# lime-lemon.net
KiCad netlist of a schematic drawn in EAGLE
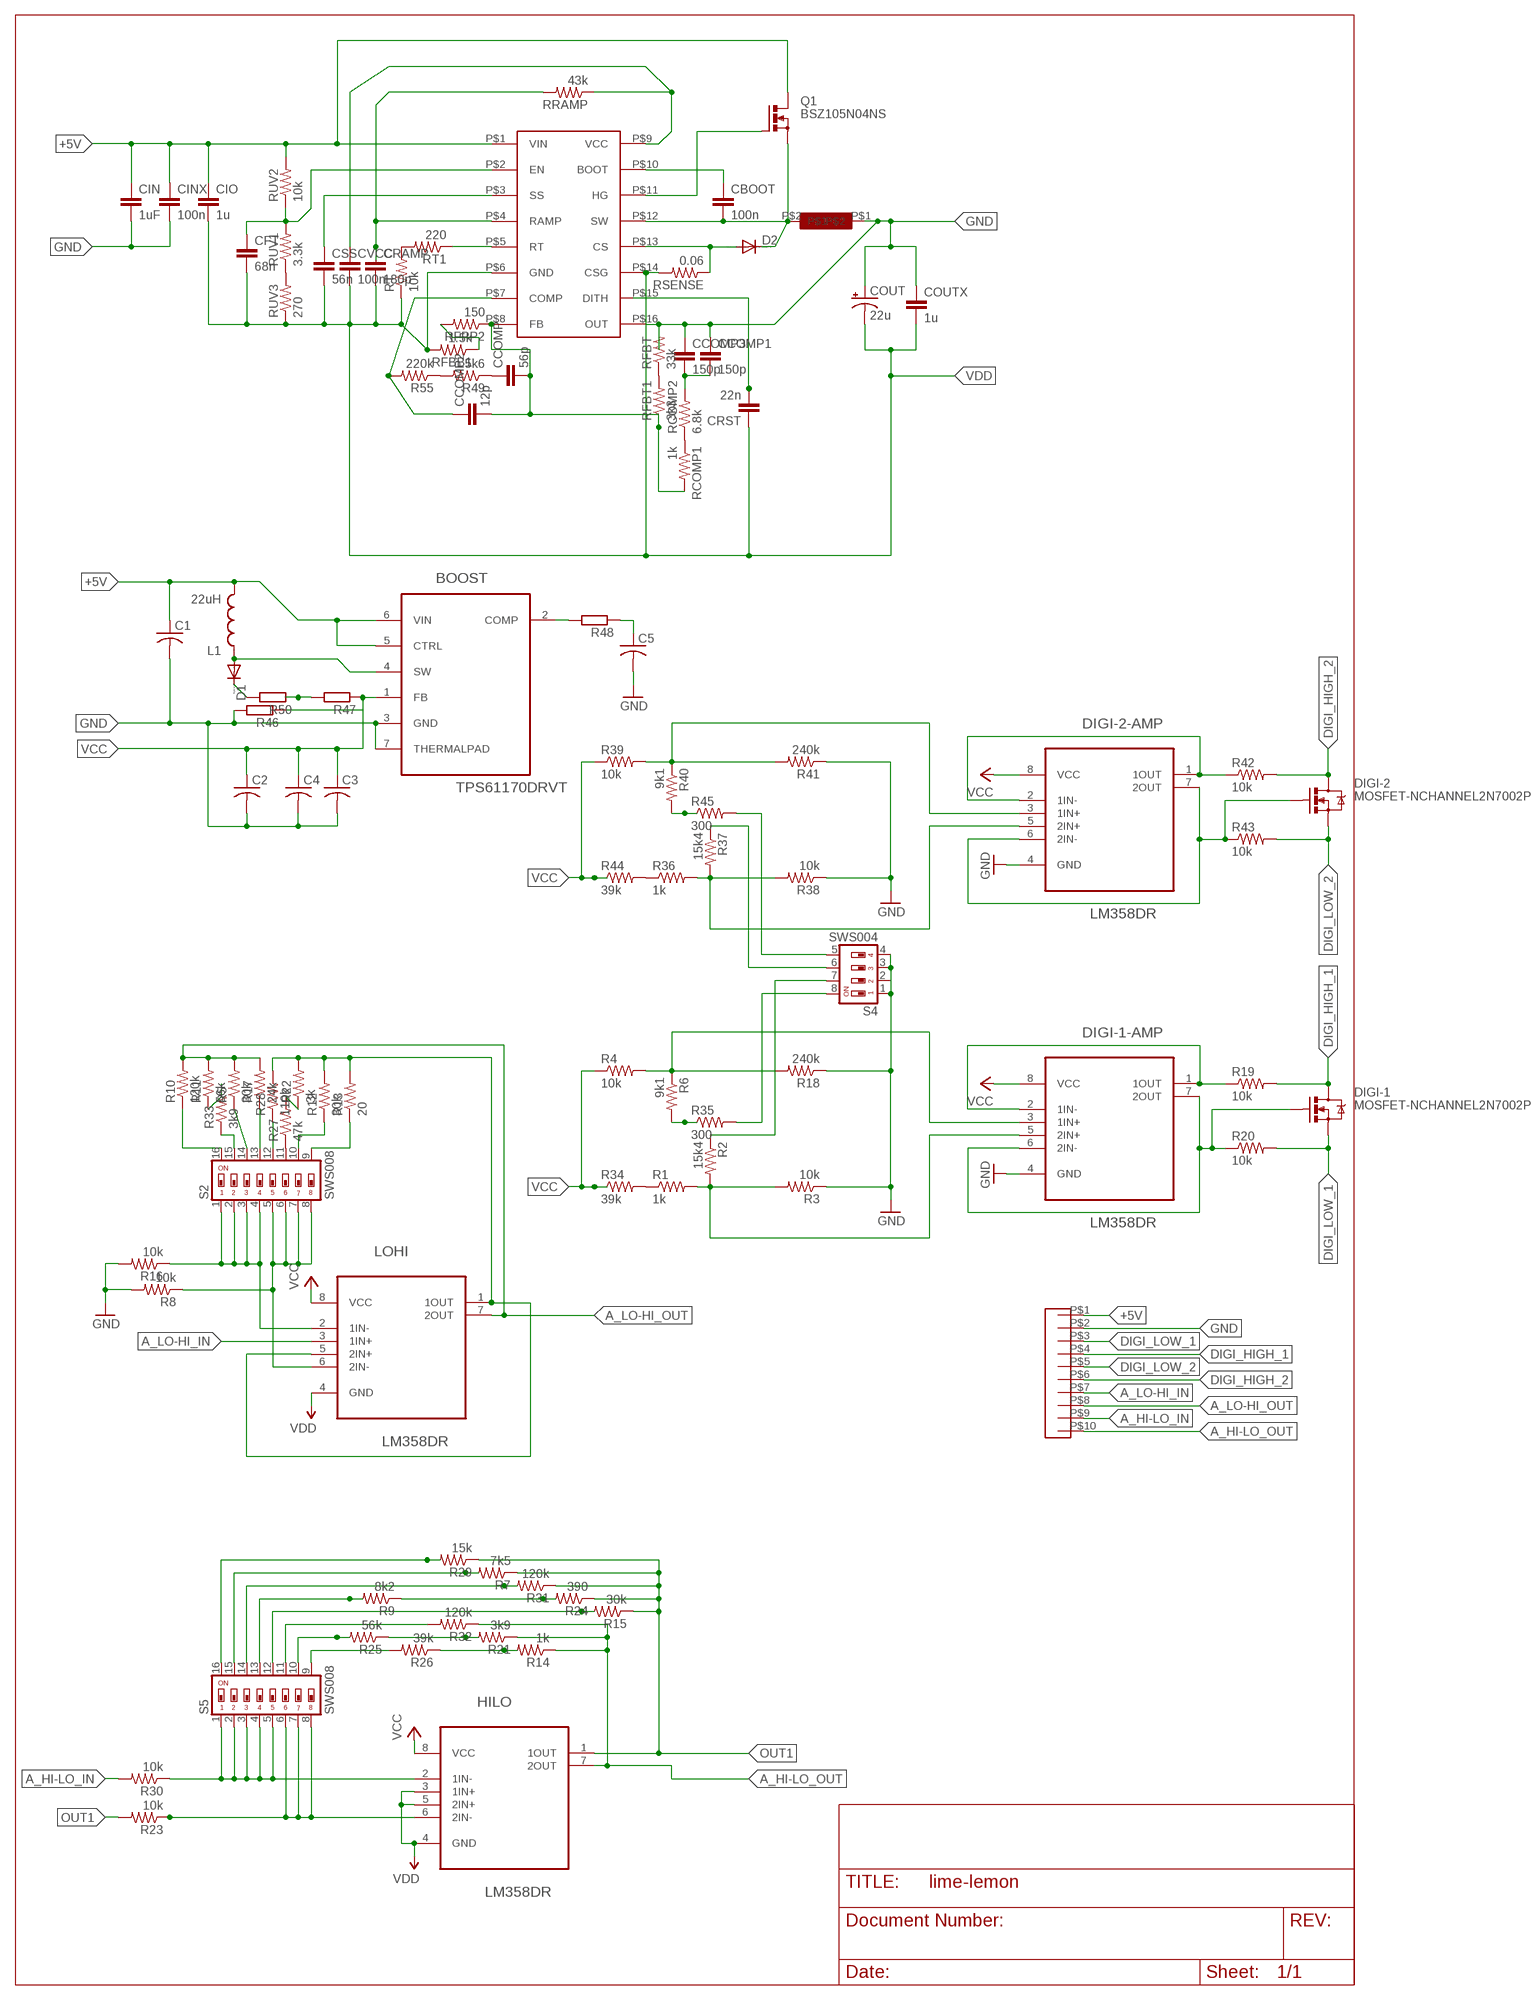
[diagram p0: schematic, sheet 1]

(export (version "E")
  (design (tool "Eeschema 10.0.6"))
  (components
    (comp (ref "BOOST")
      (value "TPS61170DRVT")
      (footprint "eagle-import:SON65P210X210X80-7N")
      (libsource (lib "eagle-import") (part "TPS61170DRVT"))
    )
    (comp (ref "C1")
      (value "C-USC1206")
      (footprint "eagle-import:C1206")
      (libsource (lib "eagle-import") (part "C-USC1206"))
    )
    (comp (ref "C2")
      (value "C-USC0805")
      (footprint "eagle-import:C0805")
      (libsource (lib "eagle-import") (part "C-USC0805"))
    )
    (comp (ref "C3")
      (value "C-USC1206")
      (footprint "eagle-import:C1206")
      (libsource (lib "eagle-import") (part "C-USC1206"))
    )
    (comp (ref "C4")
      (value "C-USC1206")
      (footprint "eagle-import:C1206")
      (libsource (lib "eagle-import") (part "C-USC1206"))
    )
    (comp (ref "C5")
      (value "C-USC1206")
      (footprint "eagle-import:C1206")
      (libsource (lib "eagle-import") (part "C-USC1206"))
    )
    (comp (ref "CBOOT")
      (value "100n")
      (footprint "eagle-import:C0805")
      (libsource (lib "eagle-import") (part "C-EUC0805"))
    )
    (comp (ref "CCOMP")
      (value "56p")
      (footprint "eagle-import:C0805")
      (libsource (lib "eagle-import") (part "C-EUC0805"))
    )
    (comp (ref "CCOMP1")
      (value "150p")
      (footprint "eagle-import:C0805")
      (libsource (lib "eagle-import") (part "C-EUC0805"))
    )
    (comp (ref "CCOMP2")
      (value "12p")
      (footprint "eagle-import:C0805")
      (libsource (lib "eagle-import") (part "C-EUC0805"))
    )
    (comp (ref "CCOMP3")
      (value "150p")
      (footprint "eagle-import:C0805")
      (libsource (lib "eagle-import") (part "C-EUC0805"))
    )
    (comp (ref "CFT")
      (value "68n")
      (footprint "eagle-import:C0805")
      (libsource (lib "eagle-import") (part "C-EUC0805"))
    )
    (comp (ref "CIN")
      (value "1uF")
      (footprint "eagle-import:C0805")
      (libsource (lib "eagle-import") (part "C-EUC0805"))
    )
    (comp (ref "CINX")
      (value "100n")
      (footprint "eagle-import:C0805")
      (libsource (lib "eagle-import") (part "C-EUC0805"))
    )
    (comp (ref "CIO")
      (value "1u")
      (footprint "eagle-import:C0805")
      (libsource (lib "eagle-import") (part "C-EUC0805"))
    )
    (comp (ref "COUT")
      (value "22u")
      (footprint "eagle-import:E5-5")
      (libsource (lib "eagle-import") (part "CPOL-USE5-5"))
    )
    (comp (ref "COUTX")
      (value "1u")
      (footprint "eagle-import:C0805")
      (libsource (lib "eagle-import") (part "C-EUC0805"))
    )
    (comp (ref "CRAMP")
      (value "180p")
      (footprint "eagle-import:C0805")
      (libsource (lib "eagle-import") (part "C-EUC0805"))
    )
    (comp (ref "CRST")
      (value "22n")
      (footprint "eagle-import:C0805")
      (libsource (lib "eagle-import") (part "C-EUC0805"))
    )
    (comp (ref "CSS")
      (value "56n")
      (footprint "eagle-import:C0805")
      (libsource (lib "eagle-import") (part "C-EUC0805"))
    )
    (comp (ref "CVCC")
      (value "100n")
      (footprint "eagle-import:C0805")
      (libsource (lib "eagle-import") (part "C-EUC0805"))
    )
    (comp (ref "D1")
      (value "DIODE-SOD123")
      (footprint "eagle-import:SOD123")
      (libsource (lib "eagle-import") (part "DIODE-SOD123"))
    )
    (comp (ref "D2")
      (value "DIODE-SOD123")
      (footprint "eagle-import:SOD123")
      (libsource (lib "eagle-import") (part "DIODE-SOD123"))
    )
    (comp (ref "DIGI-1")
      (value "MOSFET-NCHANNEL2N7002PW")
      (footprint "eagle-import:SOT323")
      (libsource (lib "eagle-import") (part "MOSFET-NCHANNEL2N7002PW"))
    )
    (comp (ref "DIGI-1-AMP")
      (value "LM358DR")
      (footprint "eagle-import:SOIC127P600X175-8N")
      (libsource (lib "eagle-import") (part "LM358DR"))
    )
    (comp (ref "DIGI-2")
      (value "MOSFET-NCHANNEL2N7002PW")
      (footprint "eagle-import:SOT323")
      (libsource (lib "eagle-import") (part "MOSFET-NCHANNEL2N7002PW"))
    )
    (comp (ref "DIGI-2-AMP")
      (value "LM358DR")
      (footprint "eagle-import:SOIC127P600X175-8N")
      (libsource (lib "eagle-import") (part "LM358DR"))
    )
    (comp (ref "HILO")
      (value "LM358DR")
      (footprint "eagle-import:SOIC127P600X175-8N")
      (libsource (lib "eagle-import") (part "LM358DR"))
    )
    (comp (ref "L1")
      (value "22uH")
      (footprint "eagle-import:SRN6045")
      (libsource (lib "eagle-import") (part "INDUCTORBOURNS_SRN6045"))
    )
    (comp (ref "LOHI")
      (value "LM358DR")
      (footprint "eagle-import:SOIC127P600X175-8N")
      (libsource (lib "eagle-import") (part "LM358DR"))
    )
    (comp (ref "Q1")
      (value "BSZ105N04NS")
      (footprint "eagle-import:PG-TDSON-8")
      (libsource (lib "eagle-import") (part "BSZ105N04NS"))
    )
    (comp (ref "R1")
      (value "1k")
      (footprint "eagle-import:R0805")
      (libsource (lib "eagle-import") (part "R-US_R0805"))
    )
    (comp (ref "R2")
      (value "15k4")
      (footprint "eagle-import:R0805")
      (libsource (lib "eagle-import") (part "R-US_R0805"))
    )
    (comp (ref "R3")
      (value "10k")
      (footprint "eagle-import:R0805")
      (libsource (lib "eagle-import") (part "R-US_R0805"))
    )
    (comp (ref "R4")
      (value "10k")
      (footprint "eagle-import:R0805")
      (libsource (lib "eagle-import") (part "R-US_R0805"))
    )
    (comp (ref "R5")
      (value "30k")
      (footprint "eagle-import:R0805")
      (libsource (lib "eagle-import") (part "R-US_R0805"))
    )
    (comp (ref "R6")
      (value "9k1")
      (footprint "eagle-import:R0805")
      (libsource (lib "eagle-import") (part "R-US_R0805"))
    )
    (comp (ref "R7")
      (value "7k5")
      (footprint "eagle-import:R0805")
      (libsource (lib "eagle-import") (part "R-US_R0805"))
    )
    (comp (ref "R8")
      (value "10k")
      (footprint "eagle-import:R0805")
      (libsource (lib "eagle-import") (part "R-US_R0805"))
    )
    (comp (ref "R9")
      (value "8k2")
      (footprint "eagle-import:R0805")
      (libsource (lib "eagle-import") (part "R-US_R0805"))
    )
    (comp (ref "R10")
      (value "120k")
      (footprint "eagle-import:R0805")
      (libsource (lib "eagle-import") (part "R-US_R0805"))
    )
    (comp (ref "R11")
      (value "56k")
      (footprint "eagle-import:R0805")
      (libsource (lib "eagle-import") (part "R-US_R0805"))
    )
    (comp (ref "R12")
      (value "30k")
      (footprint "eagle-import:R0805")
      (libsource (lib "eagle-import") (part "R-US_R0805"))
    )
    (comp (ref "R13")
      (value "20")
      (footprint "eagle-import:R0805")
      (libsource (lib "eagle-import") (part "R-US_R0805"))
    )
    (comp (ref "R14")
      (value "1k")
      (footprint "eagle-import:R0805")
      (libsource (lib "eagle-import") (part "R-US_R0805"))
    )
    (comp (ref "R15")
      (value "30k")
      (footprint "eagle-import:R0805")
      (libsource (lib "eagle-import") (part "R-US_R0805"))
    )
    (comp (ref "R16")
      (value "10k")
      (footprint "eagle-import:R0805")
      (libsource (lib "eagle-import") (part "R-US_R0805"))
    )
    (comp (ref "R17")
      (value "24k")
      (footprint "eagle-import:R0805")
      (libsource (lib "eagle-import") (part "R-US_R0805"))
    )
    (comp (ref "R18")
      (value "240k")
      (footprint "eagle-import:R0805")
      (libsource (lib "eagle-import") (part "R-US_R0805"))
    )
    (comp (ref "R19")
      (value "10k")
      (footprint "eagle-import:R0805")
      (libsource (lib "eagle-import") (part "R-US_R0805"))
    )
    (comp (ref "R20")
      (value "10k")
      (footprint "eagle-import:R0805")
      (libsource (lib "eagle-import") (part "R-US_R0805"))
    )
    (comp (ref "R21")
      (value "3k9")
      (footprint "eagle-import:R0805")
      (libsource (lib "eagle-import") (part "R-US_R0805"))
    )
    (comp (ref "R22")
      (value "3k")
      (footprint "eagle-import:R0805")
      (libsource (lib "eagle-import") (part "R-US_R0805"))
    )
    (comp (ref "R23")
      (value "10k")
      (footprint "eagle-import:R0805")
      (libsource (lib "eagle-import") (part "R-US_R0805"))
    )
    (comp (ref "R24")
      (value "390")
      (footprint "eagle-import:R0805")
      (libsource (lib "eagle-import") (part "R-US_R0805"))
    )
    (comp (ref "R25")
      (value "56k")
      (footprint "eagle-import:R0805")
      (libsource (lib "eagle-import") (part "R-US_R0805"))
    )
    (comp (ref "R26")
      (value "39k")
      (footprint "eagle-import:R0805")
      (libsource (lib "eagle-import") (part "R-US_R0805"))
    )
    (comp (ref "R27")
      (value "47k")
      (footprint "eagle-import:R0805")
      (libsource (lib "eagle-import") (part "R-US_R0805"))
    )
    (comp (ref "R28")
      (value "110k")
      (footprint "eagle-import:R0805")
      (libsource (lib "eagle-import") (part "R-US_R0805"))
    )
    (comp (ref "R29")
      (value "15k")
      (footprint "eagle-import:R0805")
      (libsource (lib "eagle-import") (part "R-US_R0805"))
    )
    (comp (ref "R30")
      (value "10k")
      (footprint "eagle-import:R0805")
      (libsource (lib "eagle-import") (part "R-US_R0805"))
    )
    (comp (ref "R31")
      (value "120k")
      (footprint "eagle-import:R0805")
      (libsource (lib "eagle-import") (part "R-US_R0805"))
    )
    (comp (ref "R32")
      (value "120k")
      (footprint "eagle-import:R0805")
      (libsource (lib "eagle-import") (part "R-US_R0805"))
    )
    (comp (ref "R33")
      (value "3k9")
      (footprint "eagle-import:R0805")
      (libsource (lib "eagle-import") (part "R-US_R0805"))
    )
    (comp (ref "R34")
      (value "39k")
      (footprint "eagle-import:R0805")
      (libsource (lib "eagle-import") (part "R-US_R0805"))
    )
    (comp (ref "R35")
      (value "300")
      (footprint "eagle-import:R0805")
      (libsource (lib "eagle-import") (part "R-US_R0805"))
    )
    (comp (ref "R36")
      (value "1k")
      (footprint "eagle-import:R0805")
      (libsource (lib "eagle-import") (part "R-US_R0805"))
    )
    (comp (ref "R37")
      (value "15k4")
      (footprint "eagle-import:R0805")
      (libsource (lib "eagle-import") (part "R-US_R0805"))
    )
    (comp (ref "R38")
      (value "10k")
      (footprint "eagle-import:R0805")
      (libsource (lib "eagle-import") (part "R-US_R0805"))
    )
    (comp (ref "R39")
      (value "10k")
      (footprint "eagle-import:R0805")
      (libsource (lib "eagle-import") (part "R-US_R0805"))
    )
    (comp (ref "R40")
      (value "9k1")
      (footprint "eagle-import:R0805")
      (libsource (lib "eagle-import") (part "R-US_R0805"))
    )
    (comp (ref "R41")
      (value "240k")
      (footprint "eagle-import:R0805")
      (libsource (lib "eagle-import") (part "R-US_R0805"))
    )
    (comp (ref "R42")
      (value "10k")
      (footprint "eagle-import:R0805")
      (libsource (lib "eagle-import") (part "R-US_R0805"))
    )
    (comp (ref "R43")
      (value "10k")
      (footprint "eagle-import:R0805")
      (libsource (lib "eagle-import") (part "R-US_R0805"))
    )
    (comp (ref "R44")
      (value "39k")
      (footprint "eagle-import:R0805")
      (libsource (lib "eagle-import") (part "R-US_R0805"))
    )
    (comp (ref "R45")
      (value "300")
      (footprint "eagle-import:R0805")
      (libsource (lib "eagle-import") (part "R-US_R0805"))
    )
    (comp (ref "R46")
      (value "R-EU_R0805")
      (footprint "eagle-import:R0805")
      (libsource (lib "eagle-import") (part "R-EU_R0805"))
    )
    (comp (ref "R47")
      (value "R-EU_R0805")
      (footprint "eagle-import:R0805")
      (libsource (lib "eagle-import") (part "R-EU_R0805"))
    )
    (comp (ref "R48")
      (value "R-EU_R0805")
      (footprint "eagle-import:R0805")
      (libsource (lib "eagle-import") (part "R-EU_R0805"))
    )
    (comp (ref "R49")
      (value "5k6")
      (footprint "eagle-import:R0805")
      (libsource (lib "eagle-import") (part "R-US_R0805"))
    )
    (comp (ref "R50")
      (value "R-EU_R0805")
      (footprint "eagle-import:R0805")
      (libsource (lib "eagle-import") (part "R-EU_R0805"))
    )
    (comp (ref "R55")
      (value "220k")
      (footprint "eagle-import:R0805")
      (libsource (lib "eagle-import") (part "R-US_R0805"))
    )
    (comp (ref "RCOMP1")
      (value "1k")
      (footprint "eagle-import:R0805")
      (libsource (lib "eagle-import") (part "R-US_R0805"))
    )
    (comp (ref "RCOMP2")
      (value "6.8k")
      (footprint "eagle-import:R0805")
      (libsource (lib "eagle-import") (part "R-US_R0805"))
    )
    (comp (ref "RFBB1")
      (value "1.5k")
      (footprint "eagle-import:R0805")
      (libsource (lib "eagle-import") (part "R-US_R0805"))
    )
    (comp (ref "RFBT")
      (value "33k")
      (footprint "eagle-import:R0805")
      (libsource (lib "eagle-import") (part "R-US_R0805"))
    )
    (comp (ref "RFBT1")
      (value "3k3")
      (footprint "eagle-import:R0805")
      (libsource (lib "eagle-import") (part "R-US_R0805"))
    )
    (comp (ref "RFPP2")
      (value "150")
      (footprint "eagle-import:R0805")
      (libsource (lib "eagle-import") (part "R-US_R0805"))
    )
    (comp (ref "RRAMP")
      (value "43k")
      (footprint "eagle-import:R0805")
      (libsource (lib "eagle-import") (part "R-US_R0805"))
    )
    (comp (ref "RSENSE")
      (value "0.06")
      (footprint "eagle-import:R0805")
      (libsource (lib "eagle-import") (part "R-US_R0805"))
    )
    (comp (ref "RT")
      (value "10k")
      (footprint "eagle-import:R0805")
      (libsource (lib "eagle-import") (part "R-US_R0805"))
    )
    (comp (ref "RT1")
      (value "220")
      (footprint "eagle-import:R0805")
      (libsource (lib "eagle-import") (part "R-US_R0805"))
    )
    (comp (ref "RUV1")
      (value "3.3k")
      (footprint "eagle-import:R0805")
      (libsource (lib "eagle-import") (part "R-US_R0805"))
    )
    (comp (ref "RUV2")
      (value "10k")
      (footprint "eagle-import:R0805")
      (libsource (lib "eagle-import") (part "R-US_R0805"))
    )
    (comp (ref "RUV3")
      (value "270")
      (footprint "eagle-import:R0805")
      (libsource (lib "eagle-import") (part "R-US_R0805"))
    )
    (comp (ref "S2")
      (value "SWS008")
      (footprint "eagle-import:SMS-008")
      (libsource (lib "eagle-import") (part "SWS008"))
    )
    (comp (ref "S4")
      (value "SWS004")
      (footprint "eagle-import:SMS-004")
      (libsource (lib "eagle-import") (part "SWS004"))
    )
    (comp (ref "S5")
      (value "SWS008")
      (footprint "eagle-import:SMS-008")
      (libsource (lib "eagle-import") (part "SWS008"))
    )
    (comp (ref "U$1")
      (value "5.08PITCHTERMINAL")
      (footprint "eagle-import:10KPL508")
      (libsource (lib "eagle-import") (part "5.08PITCHTERMINAL"))
    )
    (comp (ref "U$2")
      (value "LM5088")
      (footprint "eagle-import:LM5088")
      (libsource (lib "eagle-import") (part "LM5088"))
    )
    (comp (ref "U$3")
      (value "KLICK_INDUCTOR01")
      (footprint "eagle-import:KLICK_INDUCTOR01")
      (libsource (lib "eagle-import") (part "KLICK_INDUCTOR01"))
    )
  )
  (nets
    (net (code "1") (name "+5V") (class "Default")
      (node (ref "BOOST") (pin "5") (pinfunction "CTRL_5") (pintype "input"))
      (node (ref "BOOST") (pin "6") (pinfunction "VIN_6") (pintype "power_in"))
      (node (ref "C1") (pin "1") (pinfunction "1_1") (pintype "passive"))
      (node (ref "CIN") (pin "1") (pinfunction "1_1") (pintype "passive"))
      (node (ref "CINX") (pin "1") (pinfunction "1_1") (pintype "passive"))
      (node (ref "CIO") (pin "1") (pinfunction "1_1") (pintype "passive"))
      (node (ref "L1") (pin "2") (pinfunction "2_2") (pintype "passive"))
      (node (ref "Q1") (pin "5") (pinfunction "D_5") (pintype "passive"))
      (node (ref "Q1") (pin "6") (pinfunction "D_6") (pintype "passive"))
      (node (ref "Q1") (pin "7") (pinfunction "D_7") (pintype "passive"))
      (node (ref "Q1") (pin "8") (pinfunction "D_8") (pintype "passive"))
      (node (ref "Q1") (pin "TH") (pinfunction "D_TH") (pintype "passive"))
      (node (ref "RUV2") (pin "2") (pinfunction "2_2") (pintype "passive"))
      (node (ref "U$1") (pin "P$1") (pinfunction "P$1_P$1") (pintype "bidirectional"))
      (node (ref "U$2") (pin "P$1") (pinfunction "VIN_P$1") (pintype "bidirectional"))
    )
    (net (code "2") (name "A_HI-LO_IN") (class "Default")
      (node (ref "R30") (pin "2") (pinfunction "2_2") (pintype "passive"))
      (node (ref "U$1") (pin "P$9") (pinfunction "P$9_P$9") (pintype "bidirectional"))
    )
    (net (code "3") (name "A_HI-LO_OUT") (class "Default")
      (node (ref "HILO") (pin "7") (pinfunction "2OUT_7") (pintype "output"))
      (node (ref "R14") (pin "1") (pinfunction "1_1") (pintype "passive"))
      (node (ref "R21") (pin "1") (pinfunction "1_1") (pintype "passive"))
      (node (ref "R32") (pin "1") (pinfunction "1_1") (pintype "passive"))
      (node (ref "U$1") (pin "P$10") (pinfunction "P$10_P$10") (pintype "bidirectional"))
    )
    (net (code "4") (name "A_LO-HI_IN") (class "Default")
      (node (ref "LOHI") (pin "3") (pinfunction "1IN+_3") (pintype "input"))
      (node (ref "U$1") (pin "P$7") (pinfunction "P$7_P$7") (pintype "bidirectional"))
    )
    (net (code "5") (name "A_LO-HI_OUT") (class "Default")
      (node (ref "LOHI") (pin "7") (pinfunction "2OUT_7") (pintype "output"))
      (node (ref "R10") (pin "2") (pinfunction "2_2") (pintype "passive"))
      (node (ref "R11") (pin "2") (pinfunction "2_2") (pintype "passive"))
      (node (ref "R17") (pin "2") (pinfunction "2_2") (pintype "passive"))
      (node (ref "R5") (pin "2") (pinfunction "2_2") (pintype "passive"))
      (node (ref "U$1") (pin "P$8") (pinfunction "P$8_P$8") (pintype "bidirectional"))
    )
    (net (code "6") (name "DIGI_HIGH_1") (class "Default")
      (node (ref "DIGI-1") (pin "3") (pinfunction "D_3") (pintype "passive"))
      (node (ref "R19") (pin "2") (pinfunction "2_2") (pintype "passive"))
      (node (ref "U$1") (pin "P$4") (pinfunction "P$4_P$4") (pintype "bidirectional"))
    )
    (net (code "7") (name "DIGI_HIGH_2") (class "Default")
      (node (ref "DIGI-2") (pin "3") (pinfunction "D_3") (pintype "passive"))
      (node (ref "R42") (pin "2") (pinfunction "2_2") (pintype "passive"))
      (node (ref "U$1") (pin "P$6") (pinfunction "P$6_P$6") (pintype "bidirectional"))
    )
    (net (code "8") (name "DIGI_LOW_1") (class "Default")
      (node (ref "DIGI-1") (pin "2") (pinfunction "S_2") (pintype "passive"))
      (node (ref "R20") (pin "2") (pinfunction "2_2") (pintype "passive"))
      (node (ref "U$1") (pin "P$3") (pinfunction "P$3_P$3") (pintype "bidirectional"))
    )
    (net (code "9") (name "DIGI_LOW_2") (class "Default")
      (node (ref "DIGI-2") (pin "2") (pinfunction "S_2") (pintype "passive"))
      (node (ref "R43") (pin "2") (pinfunction "2_2") (pintype "passive"))
      (node (ref "U$1") (pin "P$5") (pinfunction "P$5_P$5") (pintype "bidirectional"))
    )
    (net (code "10") (name "GND") (class "Default")
      (node (ref "BOOST") (pin "3") (pinfunction "GND_3") (pintype "passive"))
      (node (ref "BOOST") (pin "7") (pinfunction "THERMALPAD_7") (pintype "passive"))
      (node (ref "C1") (pin "2") (pinfunction "2_2") (pintype "passive"))
      (node (ref "C2") (pin "2") (pinfunction "2_2") (pintype "passive"))
      (node (ref "C3") (pin "2") (pinfunction "2_2") (pintype "passive"))
      (node (ref "C4") (pin "2") (pinfunction "2_2") (pintype "passive"))
      (node (ref "C5") (pin "2") (pinfunction "2_2") (pintype "passive"))
      (node (ref "CCOMP1") (pin "1") (pinfunction "1_1") (pintype "passive"))
      (node (ref "CCOMP3") (pin "1") (pinfunction "1_1") (pintype "passive"))
      (node (ref "CIN") (pin "2") (pinfunction "2_2") (pintype "passive"))
      (node (ref "CINX") (pin "2") (pinfunction "2_2") (pintype "passive"))
      (node (ref "COUT") (pin "+") (pinfunction "+_+") (pintype "passive"))
      (node (ref "COUTX") (pin "1") (pinfunction "1_1") (pintype "passive"))
      (node (ref "DIGI-1-AMP") (pin "4") (pinfunction "GND_4") (pintype "passive"))
      (node (ref "DIGI-2-AMP") (pin "4") (pinfunction "GND_4") (pintype "passive"))
      (node (ref "R16") (pin "2") (pinfunction "2_2") (pintype "passive"))
      (node (ref "R18") (pin "1") (pinfunction "1_1") (pintype "passive"))
      (node (ref "R3") (pin "1") (pinfunction "1_1") (pintype "passive"))
      (node (ref "R38") (pin "1") (pinfunction "1_1") (pintype "passive"))
      (node (ref "R41") (pin "1") (pinfunction "1_1") (pintype "passive"))
      (node (ref "R46") (pin "2") (pinfunction "2_2") (pintype "passive"))
      (node (ref "R8") (pin "2") (pinfunction "2_2") (pintype "passive"))
      (node (ref "RFBT") (pin "2") (pinfunction "2_2") (pintype "passive"))
      (node (ref "S4") (pin "1") (pinfunction "1_1") (pintype "passive"))
      (node (ref "S4") (pin "2") (pinfunction "2_2") (pintype "passive"))
      (node (ref "S4") (pin "3") (pinfunction "3_3") (pintype "passive"))
      (node (ref "S4") (pin "4") (pinfunction "4_4") (pintype "passive"))
      (node (ref "U$1") (pin "P$2") (pinfunction "P$2_P$2") (pintype "bidirectional"))
      (node (ref "U$2") (pin "P$16") (pinfunction "OUT_P$16") (pintype "bidirectional"))
      (node (ref "U$3") (pin "P$1") (pinfunction "P$1_P$1") (pintype "bidirectional"))
    )
    (net (code "11") (name "Net-(BOOST-COMP)") (class "Default")
      (node (ref "BOOST") (pin "2") (pinfunction "COMP_2") (pintype "output"))
      (node (ref "R48") (pin "2") (pinfunction "2_2") (pintype "passive"))
    )
    (net (code "12") (name "Net-(BOOST-SW)") (class "Default")
      (node (ref "BOOST") (pin "4") (pinfunction "SW_4") (pintype "input"))
      (node (ref "D1") (pin "A") (pinfunction "A_A") (pintype "passive"))
      (node (ref "L1") (pin "1") (pinfunction "1_1") (pintype "passive"))
    )
    (net (code "13") (name "Net-(C5-Pad1)") (class "Default")
      (node (ref "C5") (pin "1") (pinfunction "1_1") (pintype "passive"))
      (node (ref "R48") (pin "1") (pinfunction "1_1") (pintype "passive"))
    )
    (net (code "14") (name "Net-(CCOMP-Pad1)") (class "Default")
      (node (ref "CCOMP") (pin "1") (pinfunction "1_1") (pintype "passive"))
      (node (ref "R49") (pin "1") (pinfunction "1_1") (pintype "passive"))
    )
    (net (code "15") (name "Net-(CCOMP1-Pad2)") (class "Default")
      (node (ref "CCOMP1") (pin "2") (pinfunction "2_2") (pintype "passive"))
      (node (ref "CCOMP3") (pin "2") (pinfunction "2_2") (pintype "passive"))
      (node (ref "RCOMP2") (pin "2") (pinfunction "2_2") (pintype "passive"))
    )
    (net (code "16") (name "Net-(D1-PadC)") (class "Default")
      (node (ref "D1") (pin "C") (pinfunction "C_C") (pintype "passive"))
      (node (ref "R50") (pin "2") (pinfunction "2_2") (pintype "passive"))
    )
    (net (code "17") (name "Net-(DIGI-1-AMP-1IN+)") (class "Default")
      (node (ref "DIGI-1-AMP") (pin "3") (pinfunction "1IN+_3") (pintype "input"))
      (node (ref "R18") (pin "2") (pinfunction "2_2") (pintype "passive"))
      (node (ref "R4") (pin "2") (pinfunction "2_2") (pintype "passive"))
      (node (ref "R6") (pin "1") (pinfunction "1_1") (pintype "passive"))
    )
    (net (code "18") (name "Net-(DIGI-1-AMP-1IN-)") (class "Default")
      (node (ref "DIGI-1-AMP") (pin "1") (pinfunction "1OUT_1") (pintype "output"))
      (node (ref "DIGI-1-AMP") (pin "2") (pinfunction "1IN-_2") (pintype "input"))
      (node (ref "R19") (pin "1") (pinfunction "1_1") (pintype "passive"))
    )
    (net (code "19") (name "Net-(DIGI-1-AMP-2IN+)") (class "Default")
      (node (ref "DIGI-1-AMP") (pin "5") (pinfunction "2IN+_5") (pintype "input"))
      (node (ref "R1") (pin "2") (pinfunction "2_2") (pintype "passive"))
      (node (ref "R2") (pin "2") (pinfunction "2_2") (pintype "passive"))
      (node (ref "R3") (pin "2") (pinfunction "2_2") (pintype "passive"))
    )
    (net (code "20") (name "Net-(DIGI-1-AMP-2IN-)") (class "Default")
      (node (ref "DIGI-1") (pin "1") (pinfunction "G_1") (pintype "passive"))
      (node (ref "DIGI-1-AMP") (pin "6") (pinfunction "2IN-_6") (pintype "input"))
      (node (ref "DIGI-1-AMP") (pin "7") (pinfunction "2OUT_7") (pintype "output"))
      (node (ref "R20") (pin "1") (pinfunction "1_1") (pintype "passive"))
    )
    (net (code "21") (name "Net-(DIGI-2-AMP-1IN+)") (class "Default")
      (node (ref "DIGI-2-AMP") (pin "3") (pinfunction "1IN+_3") (pintype "input"))
      (node (ref "R39") (pin "2") (pinfunction "2_2") (pintype "passive"))
      (node (ref "R40") (pin "1") (pinfunction "1_1") (pintype "passive"))
      (node (ref "R41") (pin "2") (pinfunction "2_2") (pintype "passive"))
    )
    (net (code "22") (name "Net-(DIGI-2-AMP-1IN-)") (class "Default")
      (node (ref "DIGI-2-AMP") (pin "1") (pinfunction "1OUT_1") (pintype "output"))
      (node (ref "DIGI-2-AMP") (pin "2") (pinfunction "1IN-_2") (pintype "input"))
      (node (ref "R42") (pin "1") (pinfunction "1_1") (pintype "passive"))
    )
    (net (code "23") (name "Net-(DIGI-2-AMP-2IN+)") (class "Default")
      (node (ref "DIGI-2-AMP") (pin "5") (pinfunction "2IN+_5") (pintype "input"))
      (node (ref "R36") (pin "2") (pinfunction "2_2") (pintype "passive"))
      (node (ref "R37") (pin "2") (pinfunction "2_2") (pintype "passive"))
      (node (ref "R38") (pin "2") (pinfunction "2_2") (pintype "passive"))
    )
    (net (code "24") (name "Net-(DIGI-2-AMP-2IN-)") (class "Default")
      (node (ref "DIGI-2") (pin "1") (pinfunction "G_1") (pintype "passive"))
      (node (ref "DIGI-2-AMP") (pin "6") (pinfunction "2IN-_6") (pintype "input"))
      (node (ref "DIGI-2-AMP") (pin "7") (pinfunction "2OUT_7") (pintype "output"))
      (node (ref "R43") (pin "1") (pinfunction "1_1") (pintype "passive"))
    )
    (net (code "25") (name "Net-(HILO-1IN-)") (class "Default")
      (node (ref "HILO") (pin "2") (pinfunction "1IN-_2") (pintype "input"))
      (node (ref "R30") (pin "1") (pinfunction "1_1") (pintype "passive"))
      (node (ref "S5") (pin "1") (pinfunction "1_1") (pintype "passive"))
      (node (ref "S5") (pin "2") (pinfunction "2_2") (pintype "passive"))
      (node (ref "S5") (pin "3") (pinfunction "3_3") (pintype "passive"))
      (node (ref "S5") (pin "4") (pinfunction "4_4") (pintype "passive"))
      (node (ref "S5") (pin "5") (pinfunction "5_5") (pintype "passive"))
    )
    (net (code "26") (name "Net-(HILO-2IN-)") (class "Default")
      (node (ref "HILO") (pin "6") (pinfunction "2IN-_6") (pintype "input"))
      (node (ref "R23") (pin "1") (pinfunction "1_1") (pintype "passive"))
      (node (ref "S5") (pin "6") (pinfunction "6_6") (pintype "passive"))
      (node (ref "S5") (pin "7") (pinfunction "7_7") (pintype "passive"))
      (node (ref "S5") (pin "8") (pinfunction "8_8") (pintype "passive"))
    )
    (net (code "27") (name "Net-(LOHI-1IN-)") (class "Default")
      (node (ref "LOHI") (pin "2") (pinfunction "1IN-_2") (pintype "input"))
      (node (ref "R16") (pin "1") (pinfunction "1_1") (pintype "passive"))
      (node (ref "S2") (pin "1") (pinfunction "1_1") (pintype "passive"))
      (node (ref "S2") (pin "2") (pinfunction "2_2") (pintype "passive"))
      (node (ref "S2") (pin "3") (pinfunction "3_3") (pintype "passive"))
      (node (ref "S2") (pin "4") (pinfunction "4_4") (pintype "passive"))
    )
    (net (code "28") (name "Net-(LOHI-1OUT)") (class "Default")
      (node (ref "LOHI") (pin "1") (pinfunction "1OUT_1") (pintype "output"))
      (node (ref "LOHI") (pin "5") (pinfunction "2IN+_5") (pintype "input"))
      (node (ref "R12") (pin "2") (pinfunction "2_2") (pintype "passive"))
      (node (ref "R13") (pin "2") (pinfunction "2_2") (pintype "passive"))
      (node (ref "R22") (pin "2") (pinfunction "2_2") (pintype "passive"))
      (node (ref "R28") (pin "2") (pinfunction "2_2") (pintype "passive"))
    )
    (net (code "29") (name "Net-(LOHI-2IN-)") (class "Default")
      (node (ref "LOHI") (pin "6") (pinfunction "2IN-_6") (pintype "input"))
      (node (ref "R8") (pin "1") (pinfunction "1_1") (pintype "passive"))
      (node (ref "S2") (pin "5") (pinfunction "5_5") (pintype "passive"))
      (node (ref "S2") (pin "6") (pinfunction "6_6") (pintype "passive"))
      (node (ref "S2") (pin "7") (pinfunction "7_7") (pintype "passive"))
      (node (ref "S2") (pin "8") (pinfunction "8_8") (pintype "passive"))
    )
    (net (code "30") (name "Net-(Q1-G)") (class "Default")
      (node (ref "Q1") (pin "4") (pinfunction "G_4") (pintype "passive"))
      (node (ref "U$2") (pin "P$11") (pinfunction "HG_P$11") (pintype "bidirectional"))
    )
    (net (code "31") (name "Net-(R1-Pad1)") (class "Default")
      (node (ref "R1") (pin "1") (pinfunction "1_1") (pintype "passive"))
      (node (ref "R34") (pin "2") (pinfunction "2_2") (pintype "passive"))
    )
    (net (code "32") (name "Net-(R2-Pad1)") (class "Default")
      (node (ref "R2") (pin "1") (pinfunction "1_1") (pintype "passive"))
      (node (ref "S4") (pin "7") (pinfunction "7_7") (pintype "passive"))
    )
    (net (code "33") (name "Net-(R5-Pad1)") (class "Default")
      (node (ref "R5") (pin "1") (pinfunction "1_1") (pintype "passive"))
      (node (ref "S2") (pin "14") (pinfunction "14_14") (pintype "passive"))
    )
    (net (code "34") (name "Net-(R7-Pad2)") (class "Default")
      (node (ref "R7") (pin "2") (pinfunction "2_2") (pintype "passive"))
      (node (ref "S5") (pin "15") (pinfunction "15_15") (pintype "passive"))
    )
    (net (code "35") (name "Net-(R9-Pad2)") (class "Default")
      (node (ref "R9") (pin "2") (pinfunction "2_2") (pintype "passive"))
      (node (ref "S5") (pin "13") (pinfunction "13_13") (pintype "passive"))
    )
    (net (code "36") (name "Net-(R10-Pad1)") (class "Default")
      (node (ref "R10") (pin "1") (pinfunction "1_1") (pintype "passive"))
      (node (ref "S2") (pin "16") (pinfunction "16_16") (pintype "passive"))
    )
    (net (code "37") (name "Net-(R11-Pad1)") (class "Default")
      (node (ref "R11") (pin "1") (pinfunction "1_1") (pintype "passive"))
      (node (ref "R33") (pin "2") (pinfunction "2_2") (pintype "passive"))
    )
    (net (code "38") (name "Net-(R12-Pad1)") (class "Default")
      (node (ref "R12") (pin "1") (pinfunction "1_1") (pintype "passive"))
      (node (ref "S2") (pin "10") (pinfunction "10_10") (pintype "passive"))
    )
    (net (code "39") (name "Net-(R13-Pad1)") (class "Default")
      (node (ref "R13") (pin "1") (pinfunction "1_1") (pintype "passive"))
      (node (ref "S2") (pin "9") (pinfunction "9_9") (pintype "passive"))
    )
    (net (code "40") (name "Net-(R14-Pad2)") (class "Default")
      (node (ref "R14") (pin "2") (pinfunction "2_2") (pintype "passive"))
      (node (ref "R26") (pin "1") (pinfunction "1_1") (pintype "passive"))
    )
    (net (code "41") (name "Net-(R15-Pad2)") (class "Default")
      (node (ref "R15") (pin "2") (pinfunction "2_2") (pintype "passive"))
      (node (ref "S5") (pin "12") (pinfunction "12_12") (pintype "passive"))
    )
    (net (code "42") (name "Net-(R17-Pad1)") (class "Default")
      (node (ref "R17") (pin "1") (pinfunction "1_1") (pintype "passive"))
      (node (ref "S2") (pin "13") (pinfunction "13_13") (pintype "passive"))
    )
    (net (code "43") (name "Net-(R21-Pad2)") (class "Default")
      (node (ref "R21") (pin "2") (pinfunction "2_2") (pintype "passive"))
      (node (ref "R25") (pin "1") (pinfunction "1_1") (pintype "passive"))
    )
    (net (code "44") (name "Net-(R22-Pad1)") (class "Default")
      (node (ref "R22") (pin "1") (pinfunction "1_1") (pintype "passive"))
      (node (ref "R27") (pin "2") (pinfunction "2_2") (pintype "passive"))
    )
    (net (code "45") (name "Net-(R24-Pad2)") (class "Default")
      (node (ref "R24") (pin "2") (pinfunction "2_2") (pintype "passive"))
      (node (ref "R9") (pin "1") (pinfunction "1_1") (pintype "passive"))
    )
    (net (code "46") (name "Net-(R25-Pad2)") (class "Default")
      (node (ref "R25") (pin "2") (pinfunction "2_2") (pintype "passive"))
      (node (ref "S5") (pin "10") (pinfunction "10_10") (pintype "passive"))
    )
    (net (code "47") (name "Net-(R26-Pad2)") (class "Default")
      (node (ref "R26") (pin "2") (pinfunction "2_2") (pintype "passive"))
      (node (ref "S5") (pin "9") (pinfunction "9_9") (pintype "passive"))
    )
    (net (code "48") (name "Net-(R27-Pad1)") (class "Default")
      (node (ref "R27") (pin "1") (pinfunction "1_1") (pintype "passive"))
      (node (ref "S2") (pin "11") (pinfunction "11_11") (pintype "passive"))
    )
    (net (code "49") (name "Net-(R28-Pad1)") (class "Default")
      (node (ref "R28") (pin "1") (pinfunction "1_1") (pintype "passive"))
      (node (ref "S2") (pin "12") (pinfunction "12_12") (pintype "passive"))
    )
    (net (code "50") (name "Net-(R29-Pad2)") (class "Default")
      (node (ref "R29") (pin "2") (pinfunction "2_2") (pintype "passive"))
      (node (ref "S5") (pin "16") (pinfunction "16_16") (pintype "passive"))
    )
    (net (code "51") (name "Net-(R31-Pad2)") (class "Default")
      (node (ref "R31") (pin "2") (pinfunction "2_2") (pintype "passive"))
      (node (ref "S5") (pin "14") (pinfunction "14_14") (pintype "passive"))
    )
    (net (code "52") (name "Net-(R32-Pad2)") (class "Default")
      (node (ref "R32") (pin "2") (pinfunction "2_2") (pintype "passive"))
      (node (ref "S5") (pin "11") (pinfunction "11_11") (pintype "passive"))
    )
    (net (code "53") (name "Net-(R33-Pad1)") (class "Default")
      (node (ref "R33") (pin "1") (pinfunction "1_1") (pintype "passive"))
      (node (ref "S2") (pin "15") (pinfunction "15_15") (pintype "passive"))
    )
    (net (code "54") (name "Net-(R35-Pad1)") (class "Default")
      (node (ref "R35") (pin "1") (pinfunction "1_1") (pintype "passive"))
      (node (ref "R6") (pin "2") (pinfunction "2_2") (pintype "passive"))
    )
    (net (code "55") (name "Net-(R35-Pad2)") (class "Default")
      (node (ref "R35") (pin "2") (pinfunction "2_2") (pintype "passive"))
      (node (ref "S4") (pin "8") (pinfunction "8_8") (pintype "passive"))
    )
    (net (code "56") (name "Net-(R36-Pad1)") (class "Default")
      (node (ref "R36") (pin "1") (pinfunction "1_1") (pintype "passive"))
      (node (ref "R44") (pin "2") (pinfunction "2_2") (pintype "passive"))
    )
    (net (code "57") (name "Net-(R37-Pad1)") (class "Default")
      (node (ref "R37") (pin "1") (pinfunction "1_1") (pintype "passive"))
      (node (ref "S4") (pin "6") (pinfunction "6_6") (pintype "passive"))
    )
    (net (code "58") (name "Net-(R40-Pad2)") (class "Default")
      (node (ref "R40") (pin "2") (pinfunction "2_2") (pintype "passive"))
      (node (ref "R45") (pin "1") (pinfunction "1_1") (pintype "passive"))
    )
    (net (code "59") (name "Net-(R45-Pad2)") (class "Default")
      (node (ref "R45") (pin "2") (pinfunction "2_2") (pintype "passive"))
      (node (ref "S4") (pin "5") (pinfunction "5_5") (pintype "passive"))
    )
    (net (code "60") (name "Net-(R47-Pad2)") (class "Default")
      (node (ref "R47") (pin "2") (pinfunction "2_2") (pintype "passive"))
      (node (ref "R50") (pin "1") (pinfunction "1_1") (pintype "passive"))
    )
    (net (code "61") (name "Net-(R49-Pad2)") (class "Default")
      (node (ref "R49") (pin "2") (pinfunction "2_2") (pintype "passive"))
      (node (ref "R55") (pin "1") (pinfunction "1_1") (pintype "passive"))
    )
    (net (code "62") (name "Net-(RCOMP1-Pad1)") (class "Default")
      (node (ref "RCOMP1") (pin "1") (pinfunction "1_1") (pintype "passive"))
      (node (ref "RCOMP2") (pin "1") (pinfunction "1_1") (pintype "passive"))
    )
    (net (code "63") (name "Net-(RFBB1-Pad1)") (class "Default")
      (node (ref "RFBB1") (pin "1") (pinfunction "1_1") (pintype "passive"))
      (node (ref "RFPP2") (pin "2") (pinfunction "2_2") (pintype "passive"))
    )
    (net (code "64") (name "Net-(RFBT-Pad1)") (class "Default")
      (node (ref "RFBT") (pin "1") (pinfunction "1_1") (pintype "passive"))
      (node (ref "RFBT1") (pin "2") (pinfunction "2_2") (pintype "passive"))
    )
    (net (code "65") (name "Net-(RT-Pad2)") (class "Default")
      (node (ref "RT") (pin "2") (pinfunction "2_2") (pintype "passive"))
      (node (ref "RT1") (pin "2") (pinfunction "2_2") (pintype "passive"))
    )
    (net (code "66") (name "Net-(RUV1-Pad1)") (class "Default")
      (node (ref "RUV1") (pin "1") (pinfunction "1_1") (pintype "passive"))
      (node (ref "RUV3") (pin "2") (pinfunction "2_2") (pintype "passive"))
    )
    (net (code "67") (name "Net-(U$2-BOOT)") (class "Default")
      (node (ref "CBOOT") (pin "1") (pinfunction "1_1") (pintype "passive"))
      (node (ref "U$2") (pin "P$10") (pinfunction "BOOT_P$10") (pintype "bidirectional"))
    )
    (net (code "68") (name "Net-(U$2-COMP)") (class "Default")
      (node (ref "CCOMP2") (pin "1") (pinfunction "1_1") (pintype "passive"))
      (node (ref "R55") (pin "2") (pinfunction "2_2") (pintype "passive"))
      (node (ref "U$2") (pin "P$7") (pinfunction "COMP_P$7") (pintype "bidirectional"))
    )
    (net (code "69") (name "Net-(U$2-CS)") (class "Default")
      (node (ref "D2") (pin "A") (pinfunction "A_A") (pintype "passive"))
      (node (ref "RSENSE") (pin "1") (pinfunction "1_1") (pintype "passive"))
      (node (ref "U$2") (pin "P$13") (pinfunction "CS_P$13") (pintype "bidirectional"))
    )
    (net (code "70") (name "Net-(U$2-DITH)") (class "Default")
      (node (ref "CRST") (pin "2") (pinfunction "2_2") (pintype "passive"))
      (node (ref "U$2") (pin "P$15") (pinfunction "DITH_P$15") (pintype "bidirectional"))
    )
    (net (code "71") (name "Net-(U$2-EN)") (class "Default")
      (node (ref "CFT") (pin "1") (pinfunction "1_1") (pintype "passive"))
      (node (ref "RUV1") (pin "2") (pinfunction "2_2") (pintype "passive"))
      (node (ref "RUV2") (pin "1") (pinfunction "1_1") (pintype "passive"))
      (node (ref "U$2") (pin "P$2") (pinfunction "EN_P$2") (pintype "bidirectional"))
    )
    (net (code "72") (name "Net-(U$2-FB)") (class "Default")
      (node (ref "CCOMP") (pin "2") (pinfunction "2_2") (pintype "passive"))
      (node (ref "CCOMP2") (pin "2") (pinfunction "2_2") (pintype "passive"))
      (node (ref "RCOMP1") (pin "2") (pinfunction "2_2") (pintype "passive"))
      (node (ref "RFBT1") (pin "1") (pinfunction "1_1") (pintype "passive"))
      (node (ref "RFPP2") (pin "1") (pinfunction "1_1") (pintype "passive"))
      (node (ref "U$2") (pin "P$8") (pinfunction "FB_P$8") (pintype "bidirectional"))
    )
    (net (code "73") (name "Net-(U$2-RAMP)") (class "Default")
      (node (ref "CRAMP") (pin "1") (pinfunction "1_1") (pintype "passive"))
      (node (ref "RRAMP") (pin "2") (pinfunction "2_2") (pintype "passive"))
      (node (ref "U$2") (pin "P$4") (pinfunction "RAMP_P$4") (pintype "bidirectional"))
    )
    (net (code "74") (name "Net-(U$2-RT)") (class "Default")
      (node (ref "RT1") (pin "1") (pinfunction "1_1") (pintype "passive"))
      (node (ref "U$2") (pin "P$5") (pinfunction "RT_P$5") (pintype "bidirectional"))
    )
    (net (code "75") (name "Net-(U$2-SS)") (class "Default")
      (node (ref "CSS") (pin "1") (pinfunction "1_1") (pintype "passive"))
      (node (ref "U$2") (pin "P$3") (pinfunction "SS_P$3") (pintype "bidirectional"))
    )
    (net (code "76") (name "Net-(U$2-SW)") (class "Default")
      (node (ref "CBOOT") (pin "2") (pinfunction "2_2") (pintype "passive"))
      (node (ref "D2") (pin "C") (pinfunction "C_C") (pintype "passive"))
      (node (ref "Q1") (pin "1") (pinfunction "S_1") (pintype "passive"))
      (node (ref "Q1") (pin "2") (pinfunction "S_2") (pintype "passive"))
      (node (ref "Q1") (pin "3") (pinfunction "S_3") (pintype "passive"))
      (node (ref "U$2") (pin "P$12") (pinfunction "SW_P$12") (pintype "bidirectional"))
      (node (ref "U$3") (pin "P$2") (pinfunction "P$2_P$2") (pintype "bidirectional"))
    )
    (net (code "77") (name "Net-(U$2-VCC)") (class "Default")
      (node (ref "CVCC") (pin "1") (pinfunction "1_1") (pintype "passive"))
      (node (ref "RRAMP") (pin "1") (pinfunction "1_1") (pintype "passive"))
      (node (ref "U$2") (pin "P$9") (pinfunction "VCC_P$9") (pintype "bidirectional"))
    )
    (net (code "78") (name "OUT1") (class "Default")
      (node (ref "HILO") (pin "1") (pinfunction "1OUT_1") (pintype "output"))
      (node (ref "R15") (pin "1") (pinfunction "1_1") (pintype "passive"))
      (node (ref "R23") (pin "2") (pinfunction "2_2") (pintype "passive"))
      (node (ref "R24") (pin "1") (pinfunction "1_1") (pintype "passive"))
      (node (ref "R29") (pin "1") (pinfunction "1_1") (pintype "passive"))
      (node (ref "R31") (pin "1") (pinfunction "1_1") (pintype "passive"))
      (node (ref "R7") (pin "1") (pinfunction "1_1") (pintype "passive"))
    )
    (net (code "79") (name "VCC") (class "Default")
      (node (ref "BOOST") (pin "1") (pinfunction "FB_1") (pintype "input"))
      (node (ref "C2") (pin "1") (pinfunction "1_1") (pintype "passive"))
      (node (ref "C3") (pin "1") (pinfunction "1_1") (pintype "passive"))
      (node (ref "C4") (pin "1") (pinfunction "1_1") (pintype "passive"))
      (node (ref "DIGI-1-AMP") (pin "8") (pinfunction "VCC_8") (pintype "power_in"))
      (node (ref "DIGI-2-AMP") (pin "8") (pinfunction "VCC_8") (pintype "power_in"))
      (node (ref "HILO") (pin "8") (pinfunction "VCC_8") (pintype "power_in"))
      (node (ref "LOHI") (pin "8") (pinfunction "VCC_8") (pintype "power_in"))
      (node (ref "R34") (pin "1") (pinfunction "1_1") (pintype "passive"))
      (node (ref "R39") (pin "1") (pinfunction "1_1") (pintype "passive"))
      (node (ref "R4") (pin "1") (pinfunction "1_1") (pintype "passive"))
      (node (ref "R44") (pin "1") (pinfunction "1_1") (pintype "passive"))
      (node (ref "R46") (pin "1") (pinfunction "1_1") (pintype "passive"))
      (node (ref "R47") (pin "1") (pinfunction "1_1") (pintype "passive"))
    )
    (net (code "80") (name "VDD") (class "Default")
      (node (ref "CFT") (pin "2") (pinfunction "2_2") (pintype "passive"))
      (node (ref "CIO") (pin "2") (pinfunction "2_2") (pintype "passive"))
      (node (ref "COUT") (pin "-") (pinfunction "-_-") (pintype "passive"))
      (node (ref "COUTX") (pin "2") (pinfunction "2_2") (pintype "passive"))
      (node (ref "CRAMP") (pin "2") (pinfunction "2_2") (pintype "passive"))
      (node (ref "CRST") (pin "1") (pinfunction "1_1") (pintype "passive"))
      (node (ref "CSS") (pin "2") (pinfunction "2_2") (pintype "passive"))
      (node (ref "CVCC") (pin "2") (pinfunction "2_2") (pintype "passive"))
      (node (ref "HILO") (pin "3") (pinfunction "1IN+_3") (pintype "input"))
      (node (ref "HILO") (pin "4") (pinfunction "GND_4") (pintype "passive"))
      (node (ref "HILO") (pin "5") (pinfunction "2IN+_5") (pintype "input"))
      (node (ref "LOHI") (pin "4") (pinfunction "GND_4") (pintype "passive"))
      (node (ref "RFBB1") (pin "2") (pinfunction "2_2") (pintype "passive"))
      (node (ref "RSENSE") (pin "2") (pinfunction "2_2") (pintype "passive"))
      (node (ref "RT") (pin "1") (pinfunction "1_1") (pintype "passive"))
      (node (ref "RUV3") (pin "1") (pinfunction "1_1") (pintype "passive"))
      (node (ref "U$2") (pin "P$14") (pinfunction "CSG_P$14") (pintype "bidirectional"))
      (node (ref "U$2") (pin "P$6") (pinfunction "GND_P$6") (pintype "bidirectional"))
    )
  )
)
